# SWEEP.net
KiCad netlist of a schematic drawn in Altium Designer
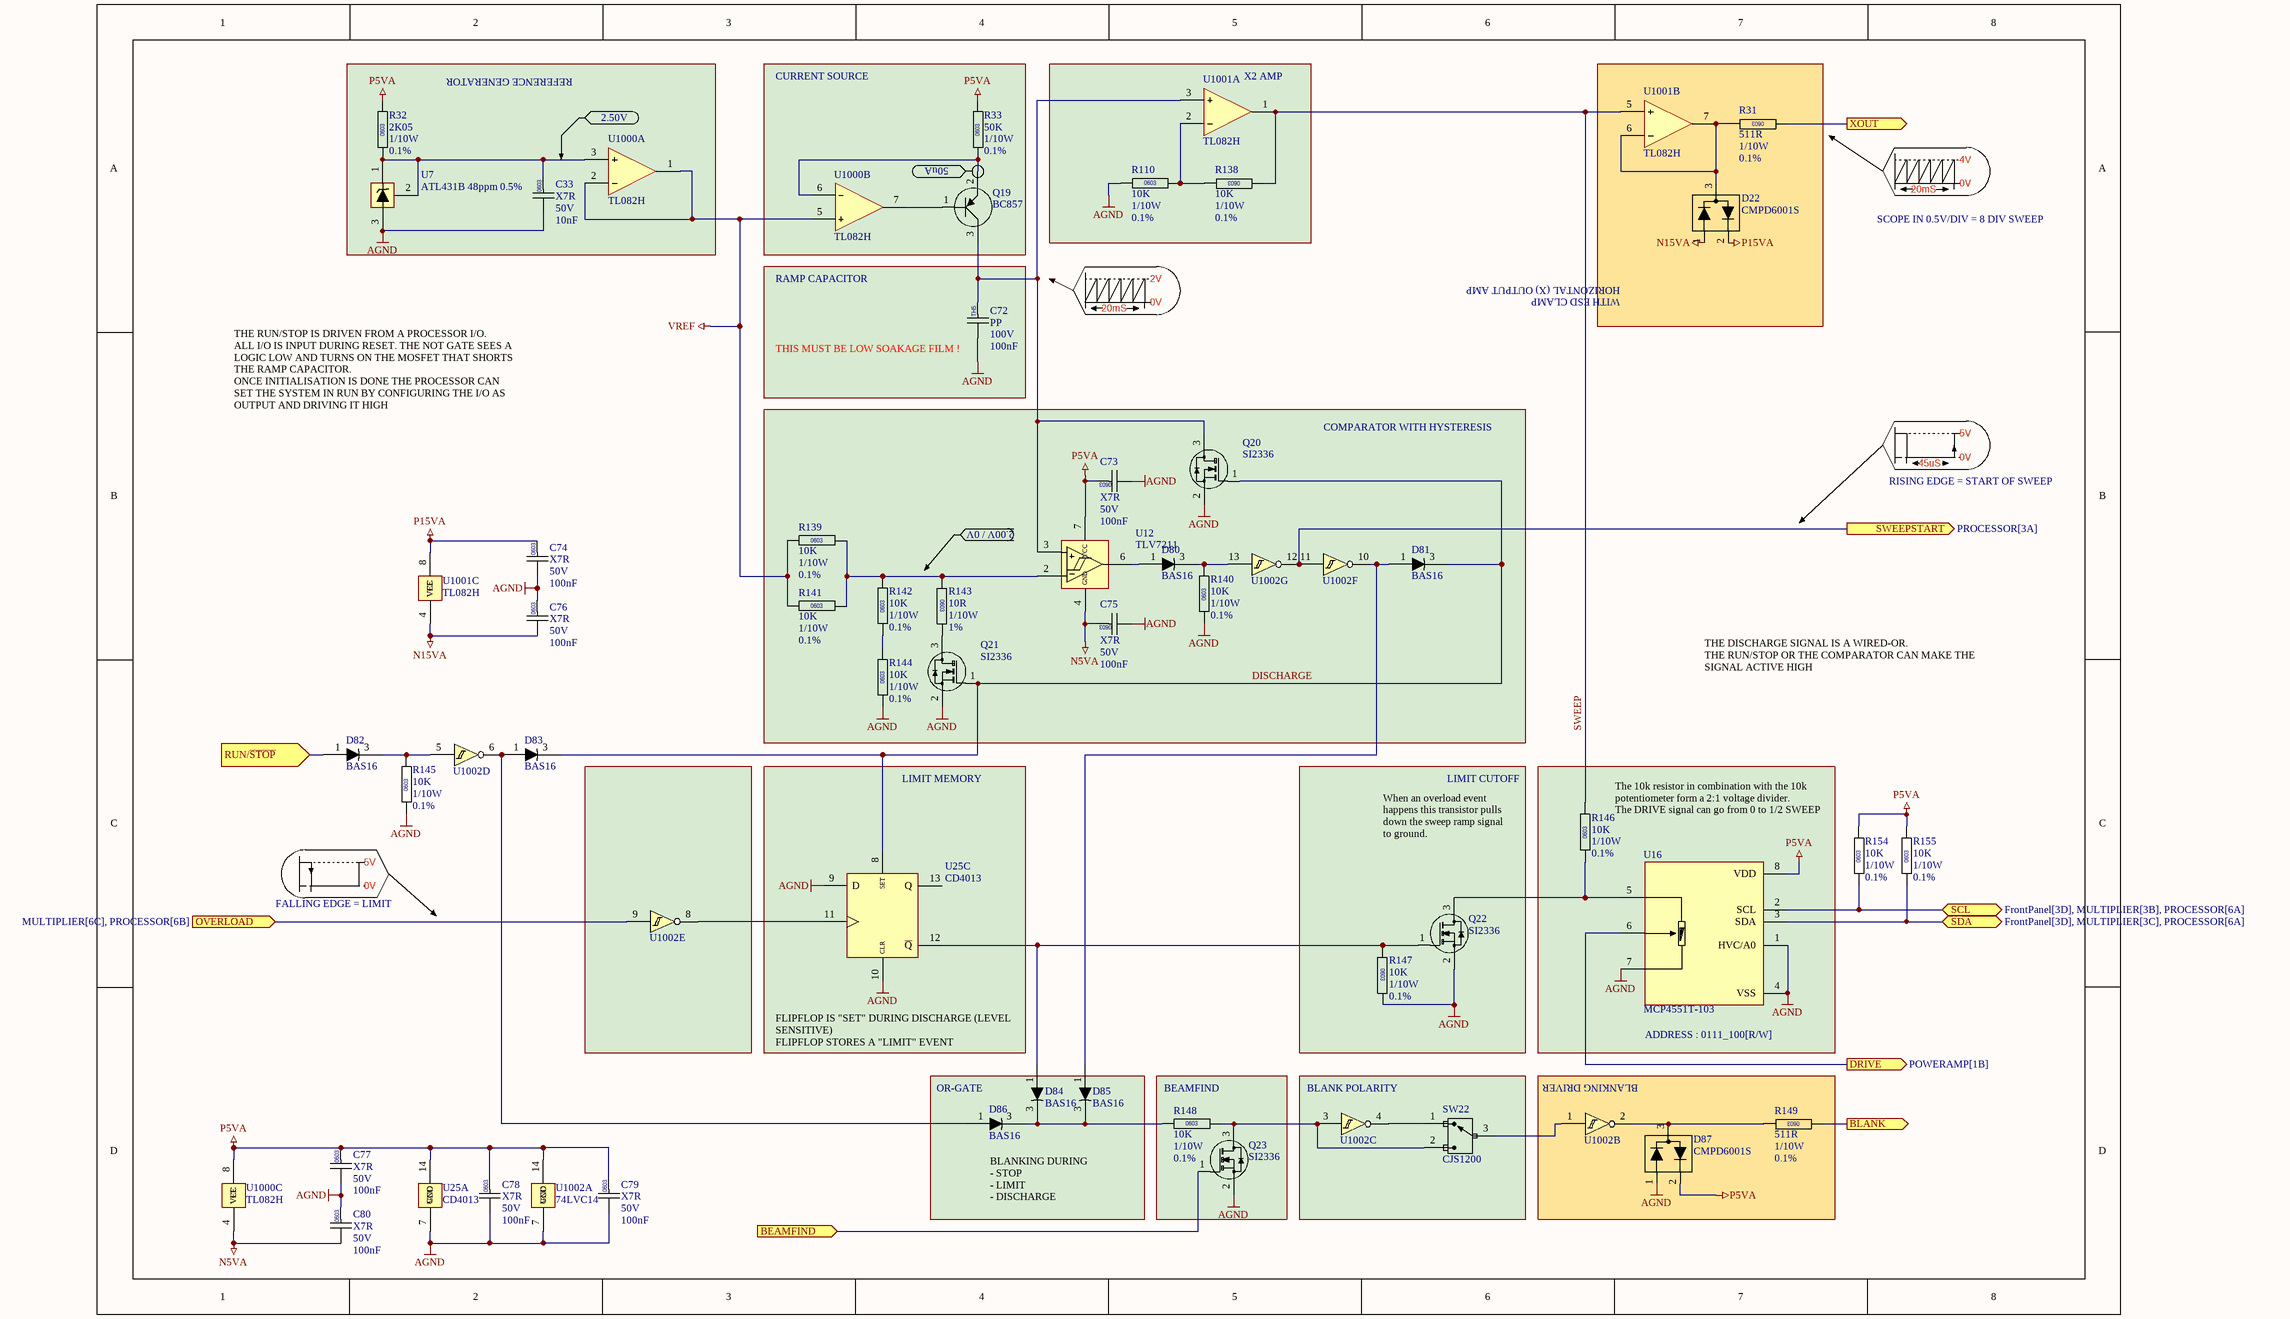
[diagram p0: SWEEP.SchDoc]

(export (version "E")
  (design (tool "Eeschema 10.0.6"))
  (components
    (comp (ref "C33")
      (value "CAP0603")
      (footprint "CAPC0603")
      (description "CAPACITOR,CERAMIC,10nF,50V,X7R,0603")
      (fields
        (field (name "DIELECTRIC") "X7R")
        (field (name "VOLTAGE") "50V")
        (field (name "CAPACITANCE") "10nF")
      )
      (libsource (lib "CAPACITORS") (part "CAPC-0603-10nF-50V-X7R"))
    )
    (comp (ref "C72")
      (value "CAPF")
      (footprint "CAPF50P720X720")
      (description "CAPACITOR,POLYPROP,100nF,100V")
      (fields
        (field (name "DIELECTRIC") "PP")
        (field (name "VOLTAGE") "100V")
        (field (name "CAPACITANCE") "100nF")
      )
      (libsource (lib "CAPACITORS") (part "CAPF-100nF-100V"))
    )
    (comp (ref "C73")
      (value "CAP0603")
      (footprint "CAPC0603")
      (description "CAPACITOR,CERAMIC,100nF,50V,X7R,0603")
      (fields
        (field (name "DIELECTRIC") "X7R")
        (field (name "VOLTAGE") "50V")
        (field (name "CAPACITANCE") "100nF")
      )
      (libsource (lib "CAPACITORS") (part "CAPC-0603-100nF-50V-X7R"))
    )
    (comp (ref "C74")
      (value "CAP0603")
      (footprint "CAPC0603")
      (description "CAPACITOR,CERAMIC,100nF,50V,X7R,0603")
      (fields
        (field (name "DIELECTRIC") "X7R")
        (field (name "VOLTAGE") "50V")
        (field (name "CAPACITANCE") "100nF")
      )
      (libsource (lib "CAPACITORS") (part "CAPC-0603-100nF-50V-X7R"))
    )
    (comp (ref "C75")
      (value "CAP0603")
      (footprint "CAPC0603")
      (description "CAPACITOR,CERAMIC,100nF,50V,X7R,0603")
      (fields
        (field (name "DIELECTRIC") "X7R")
        (field (name "VOLTAGE") "50V")
        (field (name "CAPACITANCE") "100nF")
      )
      (libsource (lib "CAPACITORS") (part "CAPC-0603-100nF-50V-X7R"))
    )
    (comp (ref "C76")
      (value "CAP0603")
      (footprint "CAPC0603")
      (description "CAPACITOR,CERAMIC,100nF,50V,X7R,0603")
      (fields
        (field (name "DIELECTRIC") "X7R")
        (field (name "VOLTAGE") "50V")
        (field (name "CAPACITANCE") "100nF")
      )
      (libsource (lib "CAPACITORS") (part "CAPC-0603-100nF-50V-X7R"))
    )
    (comp (ref "C77")
      (value "CAP0603")
      (footprint "CAPC0603")
      (description "CAPACITOR,CERAMIC,100nF,50V,X7R,0603")
      (fields
        (field (name "DIELECTRIC") "X7R")
        (field (name "VOLTAGE") "50V")
        (field (name "CAPACITANCE") "100nF")
      )
      (libsource (lib "CAPACITORS") (part "CAPC-0603-100nF-50V-X7R"))
    )
    (comp (ref "C78")
      (value "CAP0603")
      (footprint "CAPC0603")
      (description "CAPACITOR,CERAMIC,100nF,50V,X7R,0603")
      (fields
        (field (name "DIELECTRIC") "X7R")
        (field (name "VOLTAGE") "50V")
        (field (name "CAPACITANCE") "100nF")
      )
      (libsource (lib "CAPACITORS") (part "CAPC-0603-100nF-50V-X7R"))
    )
    (comp (ref "C79")
      (value "CAP0603")
      (footprint "CAPC0603")
      (description "CAPACITOR,CERAMIC,100nF,50V,X7R,0603")
      (fields
        (field (name "DIELECTRIC") "X7R")
        (field (name "VOLTAGE") "50V")
        (field (name "CAPACITANCE") "100nF")
      )
      (libsource (lib "CAPACITORS") (part "CAPC-0603-100nF-50V-X7R"))
    )
    (comp (ref "C80")
      (value "CAP0603")
      (footprint "CAPC0603")
      (description "CAPACITOR,CERAMIC,100nF,50V,X7R,0603")
      (fields
        (field (name "DIELECTRIC") "X7R")
        (field (name "VOLTAGE") "50V")
        (field (name "CAPACITANCE") "100nF")
      )
      (libsource (lib "CAPACITORS") (part "CAPC-0603-100nF-50V-X7R"))
    )
    (comp (ref "D22")
      (value "CMPD6001S")
      (footprint "SOT23")
      (description "DIODE,75V,250mA,SOT23,500pA ULTRA LOW LEAKAGE")
      (libsource (lib "DIODES") (part "DIODE-CENTRALSEMI-CMPD6001S"))
    )
    (comp (ref "D80")
      (value "BAS16")
      (footprint "SOT23")
      (description "DIODE,RECTIFIER,75V,0.3A,BAS16,SOT23")
      (libsource (lib "DIODES") (part "DIODE-RECTIFIER-DIODES-BAS16-SOT23"))
    )
    (comp (ref "D81")
      (value "BAS16")
      (footprint "SOT23")
      (description "DIODE,RECTIFIER,75V,0.3A,BAS16,SOT23")
      (libsource (lib "DIODES") (part "DIODE-RECTIFIER-DIODES-BAS16-SOT23"))
    )
    (comp (ref "D82")
      (value "BAS16")
      (footprint "SOT23")
      (description "DIODE,RECTIFIER,75V,0.3A,BAS16,SOT23")
      (libsource (lib "DIODES") (part "DIODE-RECTIFIER-DIODES-BAS16-SOT23"))
    )
    (comp (ref "D83")
      (value "BAS16")
      (footprint "SOT23")
      (description "DIODE,RECTIFIER,75V,0.3A,BAS16,SOT23")
      (libsource (lib "DIODES") (part "DIODE-RECTIFIER-DIODES-BAS16-SOT23"))
    )
    (comp (ref "D84")
      (value "BAS16")
      (footprint "SOT23")
      (description "DIODE,RECTIFIER,75V,0.3A,BAS16,SOT23")
      (libsource (lib "DIODES") (part "DIODE-RECTIFIER-DIODES-BAS16-SOT23"))
    )
    (comp (ref "D85")
      (value "BAS16")
      (footprint "SOT23")
      (description "DIODE,RECTIFIER,75V,0.3A,BAS16,SOT23")
      (libsource (lib "DIODES") (part "DIODE-RECTIFIER-DIODES-BAS16-SOT23"))
    )
    (comp (ref "D86")
      (value "BAS16")
      (footprint "SOT23")
      (description "DIODE,RECTIFIER,75V,0.3A,BAS16,SOT23")
      (libsource (lib "DIODES") (part "DIODE-RECTIFIER-DIODES-BAS16-SOT23"))
    )
    (comp (ref "D87")
      (value "CMPD6001S")
      (footprint "SOT23")
      (description "DIODE,75V,250mA,SOT23,500pA ULTRA LOW LEAKAGE")
      (libsource (lib "DIODES") (part "DIODE-CENTRALSEMI-CMPD6001S"))
    )
    (comp (ref "Q19")
      (value "BC857")
      (footprint "SOT23")
      (description "XSTR,PNP,SOT23,BC857,SOT23")
      (libsource (lib "TRANSISTORS") (part "XSTR-PNP-BC857"))
    )
    (comp (ref "Q20")
      (value "SI2336")
      (footprint "SOT23")
      (description "XSTR,NMOS,30V,4.3A,SI2336DS-T1-BE3.SOT23")
      (libsource (lib "TRANSISTORS") (part "XSTR-NMOS-VISHAY-SI2336DS-T1-BE3"))
    )
    (comp (ref "Q21")
      (value "SI2336")
      (footprint "SOT23")
      (description "XSTR,NMOS,30V,4.3A,SI2336DS-T1-BE3.SOT23")
      (libsource (lib "TRANSISTORS") (part "XSTR-NMOS-VISHAY-SI2336DS-T1-BE3"))
    )
    (comp (ref "Q22")
      (value "SI2336")
      (footprint "SOT23")
      (description "XSTR,NMOS,30V,4.3A,SI2336DS-T1-BE3.SOT23")
      (libsource (lib "TRANSISTORS") (part "XSTR-NMOS-VISHAY-SI2336DS-T1-BE3"))
    )
    (comp (ref "Q23")
      (value "SI2336")
      (footprint "SOT23")
      (description "XSTR,NMOS,30V,4.3A,SI2336DS-T1-BE3.SOT23")
      (libsource (lib "TRANSISTORS") (part "XSTR-NMOS-VISHAY-SI2336DS-T1-BE3"))
    )
    (comp (ref "R31")
      (value "511R")
      (footprint "RESC0603")
      (description "RESISTOR,511R,0.1%,100mW,0603 (1608)")
      (fields
        (field (name "POWER") "1/10W")
        (field (name "TOLERANCE") "0.1%")
        (field (name "Comment") "RESC0603")
      )
      (libsource (lib "RESISTORS") (part "RESC-0603-511R-0.1%"))
    )
    (comp (ref "R32")
      (value "2K05")
      (footprint "RESC0603")
      (description "RESISTOR,2K05,0.11%,100mW,0603 (1608)")
      (fields
        (field (name "POWER") "1/10W")
        (field (name "TOLERANCE") "0.1%")
        (field (name "Comment") "RESC0603")
      )
      (libsource (lib "RESISTORS") (part "RESC-0603-2K05-0.1%-1/10W"))
    )
    (comp (ref "R33")
      (value "50K")
      (footprint "RESC0603")
      (description "RESISTOR,50K,0.1%,100mW,0603 (1608)")
      (fields
        (field (name "POWER") "1/10W")
        (field (name "TOLERANCE") "0.1%")
        (field (name "Comment") "RESC0603")
      )
      (libsource (lib "RESISTORS") (part "RESC-0603-50K-0.1%-1/10W"))
    )
    (comp (ref "R110")
      (value "10K")
      (footprint "RESC0603")
      (description "RESISTOR,10K,0.1%,100mW,0603 (1608)")
      (fields
        (field (name "POWER") "1/10W")
        (field (name "TOLERANCE") "0.1%")
        (field (name "Comment") "RESC0603")
      )
      (libsource (lib "RESISTORS") (part "RESC-0603-10K-0.1%-1/10W"))
    )
    (comp (ref "R138")
      (value "10K")
      (footprint "RESC0603")
      (description "RESISTOR,10K,0.1%,100mW,0603 (1608)")
      (fields
        (field (name "POWER") "1/10W")
        (field (name "TOLERANCE") "0.1%")
        (field (name "Comment") "RESC0603")
      )
      (libsource (lib "RESISTORS") (part "RESC-0603-10K-0.1%-1/10W"))
    )
    (comp (ref "R139")
      (value "10K")
      (footprint "RESC0603")
      (description "RESISTOR,10K,0.1%,100mW,0603 (1608)")
      (fields
        (field (name "POWER") "1/10W")
        (field (name "TOLERANCE") "0.1%")
        (field (name "Comment") "RESC0603")
      )
      (libsource (lib "RESISTORS") (part "RESC-0603-10K-0.1%-1/10W"))
    )
    (comp (ref "R140")
      (value "10K")
      (footprint "RESC0603")
      (description "RESISTOR,10K,0.1%,100mW,0603 (1608)")
      (fields
        (field (name "POWER") "1/10W")
        (field (name "TOLERANCE") "0.1%")
        (field (name "Comment") "RESC0603")
      )
      (libsource (lib "RESISTORS") (part "RESC-0603-10K-0.1%-1/10W"))
    )
    (comp (ref "R141")
      (value "10K")
      (footprint "RESC0603")
      (description "RESISTOR,10K,0.1%,100mW,0603 (1608)")
      (fields
        (field (name "POWER") "1/10W")
        (field (name "TOLERANCE") "0.1%")
        (field (name "Comment") "RESC0603")
      )
      (libsource (lib "RESISTORS") (part "RESC-0603-10K-0.1%-1/10W"))
    )
    (comp (ref "R142")
      (value "10K")
      (footprint "RESC0603")
      (description "RESISTOR,10K,0.1%,100mW,0603 (1608)")
      (fields
        (field (name "POWER") "1/10W")
        (field (name "TOLERANCE") "0.1%")
        (field (name "Comment") "RESC0603")
      )
      (libsource (lib "RESISTORS") (part "RESC-0603-10K-0.1%-1/10W"))
    )
    (comp (ref "R143")
      (value "10R")
      (footprint "RESC0603")
      (description "RESISTOR,10R,1%,100mW,0603 (1608)")
      (fields
        (field (name "POWER") "1/10W")
        (field (name "TOLERANCE") "1%")
        (field (name "Comment") "RESC0603")
      )
      (libsource (lib "RESISTORS") (part "RESC-0603-10R-1%-1/10W"))
    )
    (comp (ref "R144")
      (value "10K")
      (footprint "RESC0603")
      (description "RESISTOR,10K,0.1%,100mW,0603 (1608)")
      (fields
        (field (name "POWER") "1/10W")
        (field (name "TOLERANCE") "0.1%")
        (field (name "Comment") "RESC0603")
      )
      (libsource (lib "RESISTORS") (part "RESC-0603-10K-0.1%-1/10W"))
    )
    (comp (ref "R145")
      (value "10K")
      (footprint "RESC0603")
      (description "RESISTOR,10K,0.1%,100mW,0603 (1608)")
      (fields
        (field (name "POWER") "1/10W")
        (field (name "TOLERANCE") "0.1%")
        (field (name "Comment") "RESC0603")
      )
      (libsource (lib "RESISTORS") (part "RESC-0603-10K-0.1%-1/10W"))
    )
    (comp (ref "R146")
      (value "10K")
      (footprint "RESC0603")
      (description "RESISTOR,10K,0.1%,100mW,0603 (1608)")
      (fields
        (field (name "POWER") "1/10W")
        (field (name "TOLERANCE") "0.1%")
        (field (name "Comment") "RESC0603")
      )
      (libsource (lib "RESISTORS") (part "RESC-0603-10K-0.1%-1/10W"))
    )
    (comp (ref "R147")
      (value "10K")
      (footprint "RESC0603")
      (description "RESISTOR,10K,0.1%,100mW,0603 (1608)")
      (fields
        (field (name "POWER") "1/10W")
        (field (name "TOLERANCE") "0.1%")
        (field (name "Comment") "RESC0603")
      )
      (libsource (lib "RESISTORS") (part "RESC-0603-10K-0.1%-1/10W"))
    )
    (comp (ref "R148")
      (value "10K")
      (footprint "RESC0603")
      (description "RESISTOR,10K,0.1%,100mW,0603 (1608)")
      (fields
        (field (name "POWER") "1/10W")
        (field (name "TOLERANCE") "0.1%")
        (field (name "Comment") "RESC0603")
      )
      (libsource (lib "RESISTORS") (part "RESC-0603-10K-0.1%-1/10W"))
    )
    (comp (ref "R149")
      (value "511R")
      (footprint "RESC0603")
      (description "RESISTOR,511R,0.1%,100mW,0603 (1608)")
      (fields
        (field (name "POWER") "1/10W")
        (field (name "TOLERANCE") "0.1%")
        (field (name "Comment") "RESC0603")
      )
      (libsource (lib "RESISTORS") (part "RESC-0603-511R-0.1%"))
    )
    (comp (ref "R154")
      (value "10K")
      (footprint "RESC0603")
      (description "RESISTOR,10K,0.1%,100mW,0603 (1608)")
      (fields
        (field (name "POWER") "1/10W")
        (field (name "TOLERANCE") "0.1%")
        (field (name "Comment") "RESC0603")
      )
      (libsource (lib "RESISTORS") (part "RESC-0603-10K-0.1%-1/10W"))
    )
    (comp (ref "R155")
      (value "10K")
      (footprint "RESC0603")
      (description "RESISTOR,10K,0.1%,100mW,0603 (1608)")
      (fields
        (field (name "POWER") "1/10W")
        (field (name "TOLERANCE") "0.1%")
        (field (name "Comment") "RESC0603")
      )
      (libsource (lib "RESISTORS") (part "RESC-0603-10K-0.1%-1/10W"))
    )
    (comp (ref "SW22")
      (value "CJS1200")
      (footprint "SWITCH-NIDEC-CJS-1200TB1")
      (description "SWITCH,SPST,SLIDE,SMD")
      (libsource (lib "SWITCH") (part "SWITCH-NIDEC-CJS-1200TB1"))
    )
    (comp (ref "U7")
      (value "ATL431B 48ppm 0.5%")
      (footprint "SOT23")
      (description "IC,REGULATOR,REFERENCE,SHUNT,0.5%,48ppm,TL431,SOT23")
      (libsource (lib "IC-ANALOG") (part "IC-TI-ATL431B-SOT23"))
    )
    (comp (ref "U12")
      (value "TLV7211")
      (footprint "SO127P600-8N")
      (description "IC,COMPARATOR,SINGLE,PUSHPULL,TI,TLV7211,SO8")
      (libsource (lib "IC-OPAMP") (part "IC-TI-TLV7211-SO8"))
    )
    (comp (ref "U16")
      (value "MCP4551T-103")
      (footprint "SO65P490-8N")
      (description "IC,DIGITAL POTMETER,257STEP,I2C,10K,MICROCHIP,MCP4551T-103")
      (libsource (lib "IC-I2C") (part "IC-MICROCHIP-MCP4551T-103"))
    )
    (comp (ref "U25")
      (value "CD4013")
      (footprint "SO127P600-14N")
      (description "IC,LOGIC,CMOS,4XXX,DUAL D-FLIPFLOP,CD4013")
      (libsource (lib "IC-4XXX") (part "IC-TI-CD4013-SO14"))
    )
    (comp (ref "U1000")
      (value "TL082H")
      (footprint "SO127P600-8N")
      (description "IC,OPAMP JFET,DUAL,TL082HIDR,SO8")
      (libsource (lib "IC-OPAMP") (part "IC-TI-TL082H-SO8"))
    )
    (comp (ref "U1001")
      (value "TL082H")
      (footprint "SO127P600-8N")
      (description "IC,OPAMP JFET,DUAL,TL082HIDR,SO8")
      (libsource (lib "IC-OPAMP") (part "IC-TI-TL082H-SO8"))
    )
    (comp (ref "U1002")
      (value "74LVC14")
      (footprint "SO127P600-14N")
      (description "IC,LOGIC,CMOS,74XX,HEX SCHMITTTRIGGER,74LVC14AS14-13,SO14")
      (libsource (lib "IC-74XX") (part "IC-DIODES-74LVC14AS14-13-SO14"))
    )
  )
  (nets
    (net (code "1") (name "/BEAMFIND") (class "Default")
      (node (ref "Q23") (pin "1") (pinfunction "G1_1") (pintype "passive"))
    )
    (net (code "2") (name "/BLANK") (class "Default") (node (ref "R149") (pin "2") (pintype "passive")))
    (net (code "3") (name "/DISCHARGE") (class "Default")
      (node (ref "D81") (pin "3") (pinfunction "K_3") (pintype "passive"))
      (node (ref "D83") (pin "3") (pinfunction "K_3") (pintype "passive"))
      (node (ref "Q20") (pin "1") (pinfunction "G1_1") (pintype "passive"))
      (node (ref "Q21") (pin "1") (pinfunction "G1_1") (pintype "passive"))
      (node (ref "U25") (pin "8") (pinfunction "SET_8") (pintype "passive"))
    )
    (net (code "4") (name "/DRIVE") (class "Default")
      (node (ref "U16") (pin "6") (pinfunction "OW_6") (pintype "passive"))
    )
    (net (code "5") (name "/OVERLOAD") (class "Default")
      (node (ref "U1002") (pin "9") (pinfunction "9_9") (pintype "passive"))
    )
    (net (code "6") (name "/RUN{slash}~{STOP}") (class "Default")
      (node (ref "D82") (pin "1") (pinfunction "A_1") (pintype "passive"))
    )
    (net (code "7") (name "/SCL") (class "Default")
      (node (ref "R154") (pin "2") (pintype "passive"))
      (node (ref "U16") (pin "2") (pinfunction "SCL_2") (pintype "passive"))
    )
    (net (code "8") (name "/SDA") (class "Default")
      (node (ref "R155") (pin "2") (pintype "passive"))
      (node (ref "U16") (pin "3") (pinfunction "SDA_3") (pintype "passive"))
    )
    (net (code "9") (name "/SWEEP") (class "Default")
      (node (ref "R138") (pin "2") (pintype "passive"))
      (node (ref "R146") (pin "1") (pintype "passive"))
      (node (ref "U1001") (pin "1") (pinfunction "O_1") (pintype "passive"))
      (node (ref "U1001") (pin "5") (pinfunction "+_5") (pintype "passive"))
    )
    (net (code "10") (name "/SWEEPSTART") (class "Default")
      (node (ref "U1002") (pin "11") (pinfunction "11_11") (pintype "passive"))
      (node (ref "U1002") (pin "12") (pinfunction "12_12") (pintype "passive"))
    )
    (net (code "11") (name "/XOUT") (class "Default") (node (ref "R31") (pin "2") (pintype "passive")))
    (net (code "12") (name "AGND") (class "Default")
      (node (ref "C33") (pin "2") (pintype "passive"))
      (node (ref "C72") (pin "2") (pintype "passive"))
      (node (ref "C73") (pin "2") (pintype "passive"))
      (node (ref "C74") (pin "2") (pintype "passive"))
      (node (ref "C75") (pin "2") (pintype "passive"))
      (node (ref "C76") (pin "1") (pintype "passive"))
      (node (ref "C77") (pin "2") (pintype "passive"))
      (node (ref "C78") (pin "2") (pintype "passive"))
      (node (ref "C79") (pin "2") (pintype "passive"))
      (node (ref "C80") (pin "1") (pintype "passive"))
      (node (ref "D87") (pin "1") (pinfunction "K_1") (pintype "passive"))
      (node (ref "Q20") (pin "2") (pinfunction "S_2") (pintype "passive"))
      (node (ref "Q21") (pin "2") (pinfunction "S_2") (pintype "passive"))
      (node (ref "Q22") (pin "2") (pinfunction "S_2") (pintype "passive"))
      (node (ref "Q23") (pin "2") (pinfunction "S_2") (pintype "passive"))
      (node (ref "R110") (pin "2") (pintype "passive"))
      (node (ref "R140") (pin "2") (pintype "passive"))
      (node (ref "R144") (pin "2") (pintype "passive"))
      (node (ref "R145") (pin "2") (pintype "passive"))
      (node (ref "R147") (pin "1") (pintype "passive"))
      (node (ref "U1002") (pin "7") (pinfunction "GND_7") (pintype "passive"))
      (node (ref "U16") (pin "1") (pinfunction "HVC/A0_1") (pintype "passive"))
      (node (ref "U16") (pin "4") (pinfunction "VSS_4") (pintype "passive"))
      (node (ref "U16") (pin "7") (pinfunction "POB_7") (pintype "passive"))
      (node (ref "U25") (pin "10") (pinfunction "CLR_10") (pintype "passive"))
      (node (ref "U25") (pin "7") (pinfunction "GND_7") (pintype "passive"))
      (node (ref "U25") (pin "9") (pinfunction "D_9") (pintype "passive"))
      (node (ref "U7") (pin "3") (pinfunction "3_3") (pintype "passive"))
    )
    (net (code "13") (name "N5VA") (class "Default")
      (node (ref "C75") (pin "1") (pintype "passive"))
      (node (ref "C80") (pin "2") (pintype "passive"))
      (node (ref "U1000") (pin "4") (pinfunction "VEE_4") (pintype "passive"))
      (node (ref "U12") (pin "4") (pinfunction "GND_4") (pintype "passive"))
    )
    (net (code "14") (name "N15VA") (class "Default")
      (node (ref "C76") (pin "2") (pintype "passive"))
      (node (ref "D22") (pin "1") (pinfunction "K_1") (pintype "passive"))
      (node (ref "U1001") (pin "4") (pinfunction "VEE_4") (pintype "passive"))
    )
    (net (code "15") (name "Net-(D80-A)") (class "Default")
      (node (ref "D80") (pin "1") (pinfunction "A_1") (pintype "passive"))
      (node (ref "U12") (pin "6") (pinfunction "OUT_6") (pintype "passive"))
    )
    (net (code "16") (name "Net-(D80-K)") (class "Default")
      (node (ref "D80") (pin "3") (pinfunction "K_3") (pintype "passive"))
      (node (ref "R140") (pin "1") (pintype "passive"))
      (node (ref "U1002") (pin "13") (pinfunction "13_13") (pintype "passive"))
    )
    (net (code "17") (name "Net-(D81-A)") (class "Default")
      (node (ref "D81") (pin "1") (pinfunction "A_1") (pintype "passive"))
      (node (ref "D85") (pin "1") (pinfunction "A_1") (pintype "passive"))
      (node (ref "U1002") (pin "10") (pinfunction "10_10") (pintype "passive"))
    )
    (net (code "18") (name "Net-(D82-K)") (class "Default")
      (node (ref "D82") (pin "3") (pinfunction "K_3") (pintype "passive"))
      (node (ref "R145") (pin "1") (pintype "passive"))
      (node (ref "U1002") (pin "5") (pinfunction "5_5") (pintype "passive"))
    )
    (net (code "19") (name "Net-(D83-A)") (class "Default")
      (node (ref "D83") (pin "1") (pinfunction "A_1") (pintype "passive"))
      (node (ref "D86") (pin "1") (pinfunction "A_1") (pintype "passive"))
      (node (ref "U1002") (pin "6") (pinfunction "6_6") (pintype "passive"))
    )
    (net (code "20") (name "Net-(D84-A)") (class "Default")
      (node (ref "D84") (pin "1") (pinfunction "A_1") (pintype "passive"))
      (node (ref "Q22") (pin "1") (pinfunction "G1_1") (pintype "passive"))
      (node (ref "R147") (pin "2") (pintype "passive"))
      (node (ref "U25") (pin "12") (pinfunction "~{Q}_12") (pintype "passive"))
    )
    (net (code "21") (name "Net-(D84-K)") (class "Default")
      (node (ref "D84") (pin "3") (pinfunction "K_3") (pintype "passive"))
      (node (ref "D85") (pin "3") (pinfunction "K_3") (pintype "passive"))
      (node (ref "D86") (pin "3") (pinfunction "K_3") (pintype "passive"))
      (node (ref "R148") (pin "2") (pintype "passive"))
    )
    (net (code "22") (name "Net-(D87-A-Pad3)") (class "Default")
      (node (ref "D87") (pin "3") (pinfunction "A_3") (pintype "passive"))
      (node (ref "R149") (pin "1") (pintype "passive"))
      (node (ref "U1002") (pin "2") (pinfunction "2_2") (pintype "passive"))
    )
    (net (code "23") (name "Net-(Q19-B)") (class "Default")
      (node (ref "Q19") (pin "1") (pinfunction "B_1") (pintype "passive"))
      (node (ref "U1000") (pin "7") (pinfunction "O_7") (pintype "passive"))
    )
    (net (code "24") (name "Net-(Q19-C)") (class "Default")
      (node (ref "C72") (pin "1") (pintype "passive"))
      (node (ref "Q19") (pin "3") (pinfunction "C_3") (pintype "passive"))
      (node (ref "Q20") (pin "3") (pinfunction "D_3") (pintype "passive"))
      (node (ref "U1001") (pin "3") (pinfunction "+_3") (pintype "passive"))
      (node (ref "U12") (pin "3") (pinfunction "+_3") (pintype "passive"))
    )
    (net (code "25") (name "Net-(Q19-E)") (class "Default")
      (node (ref "Q19") (pin "2") (pinfunction "E_2") (pintype "passive"))
      (node (ref "R33") (pin "2") (pintype "passive"))
      (node (ref "U1000") (pin "6") (pinfunction "-_6") (pintype "passive"))
    )
    (net (code "26") (name "Net-(Q21-D)") (class "Default")
      (node (ref "Q21") (pin "3") (pinfunction "D_3") (pintype "passive"))
      (node (ref "R143") (pin "1") (pintype "passive"))
    )
    (net (code "27") (name "Net-(Q22-D)") (class "Default")
      (node (ref "Q22") (pin "3") (pinfunction "D_3") (pintype "passive"))
      (node (ref "R146") (pin "2") (pintype "passive"))
      (node (ref "U16") (pin "5") (pinfunction "POA_5") (pintype "passive"))
    )
    (net (code "28") (name "Net-(Q23-D)") (class "Default")
      (node (ref "Q23") (pin "3") (pinfunction "D_3") (pintype "passive"))
      (node (ref "R148") (pin "1") (pintype "passive"))
      (node (ref "SW22") (pin "2") (pinfunction "2_2") (pintype "passive"))
      (node (ref "U1002") (pin "3") (pinfunction "3_3") (pintype "passive"))
    )
    (net (code "29") (name "Net-(R142-Pad2)") (class "Default")
      (node (ref "R142") (pin "2") (pintype "passive"))
      (node (ref "R144") (pin "1") (pintype "passive"))
    )
    (net (code "30") (name "Net-(SW22-Pad1)") (class "Default")
      (node (ref "SW22") (pin "1") (pinfunction "1_1") (pintype "passive"))
      (node (ref "U1002") (pin "4") (pinfunction "4_4") (pintype "passive"))
    )
    (net (code "31") (name "Net-(SW22-Pad3)") (class "Default")
      (node (ref "SW22") (pin "3") (pinfunction "3_3") (pintype "passive"))
      (node (ref "U1002") (pin "1") (pinfunction "1_1") (pintype "passive"))
    )
    (net (code "32") (name "Net-(U12--)") (class "Default")
      (node (ref "R139") (pin "1") (pintype "passive"))
      (node (ref "R141") (pin "1") (pintype "passive"))
      (node (ref "R142") (pin "1") (pintype "passive"))
      (node (ref "R143") (pin "2") (pintype "passive"))
      (node (ref "U12") (pin "2") (pinfunction "-_2") (pintype "passive"))
    )
    (net (code "33") (name "Net-(U25C-CLK)") (class "Default")
      (node (ref "U1002") (pin "8") (pinfunction "8_8") (pintype "passive"))
      (node (ref "U25") (pin "11") (pinfunction "CLK_11") (pintype "passive"))
    )
    (net (code "34") (name "Net-(U1000A-+)") (class "Default")
      (node (ref "C33") (pin "1") (pintype "passive"))
      (node (ref "R32") (pin "2") (pintype "passive"))
      (node (ref "U1000") (pin "3") (pinfunction "+_3") (pintype "passive"))
      (node (ref "U7") (pin "1") (pinfunction "1_1") (pintype "passive"))
      (node (ref "U7") (pin "2") (pinfunction "2_2") (pintype "passive"))
    )
    (net (code "35") (name "Net-(U1001A--)") (class "Default")
      (node (ref "R110") (pin "1") (pintype "passive"))
      (node (ref "R138") (pin "1") (pintype "passive"))
      (node (ref "U1001") (pin "2") (pinfunction "-_2") (pintype "passive"))
    )
    (net (code "36") (name "Net-(U1001B--)") (class "Default")
      (node (ref "D22") (pin "3") (pinfunction "A_3") (pintype "passive"))
      (node (ref "R31") (pin "1") (pintype "passive"))
      (node (ref "U1001") (pin "6") (pinfunction "-_6") (pintype "passive"))
      (node (ref "U1001") (pin "7") (pinfunction "O_7") (pintype "passive"))
    )
    (net (code "37") (name "P5VA") (class "Default")
      (node (ref "C73") (pin "1") (pintype "passive"))
      (node (ref "C77") (pin "1") (pintype "passive"))
      (node (ref "C78") (pin "1") (pintype "passive"))
      (node (ref "C79") (pin "1") (pintype "passive"))
      (node (ref "D87") (pin "2") (pinfunction "A_2") (pintype "passive"))
      (node (ref "R154") (pin "1") (pintype "passive"))
      (node (ref "R155") (pin "1") (pintype "passive"))
      (node (ref "R32") (pin "1") (pintype "passive"))
      (node (ref "R33") (pin "1") (pintype "passive"))
      (node (ref "U1000") (pin "8") (pinfunction "VCC_8") (pintype "passive"))
      (node (ref "U1002") (pin "14") (pinfunction "VCC_14") (pintype "passive"))
      (node (ref "U12") (pin "7") (pinfunction "VCC_7") (pintype "passive"))
      (node (ref "U16") (pin "8") (pinfunction "VDD_8") (pintype "passive"))
      (node (ref "U25") (pin "14") (pinfunction "VCC_14") (pintype "passive"))
    )
    (net (code "38") (name "P15VA") (class "Default")
      (node (ref "C74") (pin "1") (pintype "passive"))
      (node (ref "D22") (pin "2") (pinfunction "A_2") (pintype "passive"))
      (node (ref "U1001") (pin "8") (pinfunction "VCC_8") (pintype "passive"))
    )
    (net (code "39") (name "VREF") (class "Default")
      (node (ref "R139") (pin "2") (pintype "passive"))
      (node (ref "R141") (pin "2") (pintype "passive"))
      (node (ref "U1000") (pin "1") (pinfunction "O_1") (pintype "passive"))
      (node (ref "U1000") (pin "2") (pinfunction "-_2") (pintype "passive"))
      (node (ref "U1000") (pin "5") (pinfunction "+_5") (pintype "passive"))
    )
    (net (code "40") (name "unconnected-(U25C-Q-Pad13)") (class "Default")
      (node (ref "U25") (pin "13") (pinfunction "Q_13") (pintype "passive"))
    )
  )
)
